# SCH_NFC-Business-Card_2025-01-12.net
KiCad netlist of a schematic drawn in EasyEDA
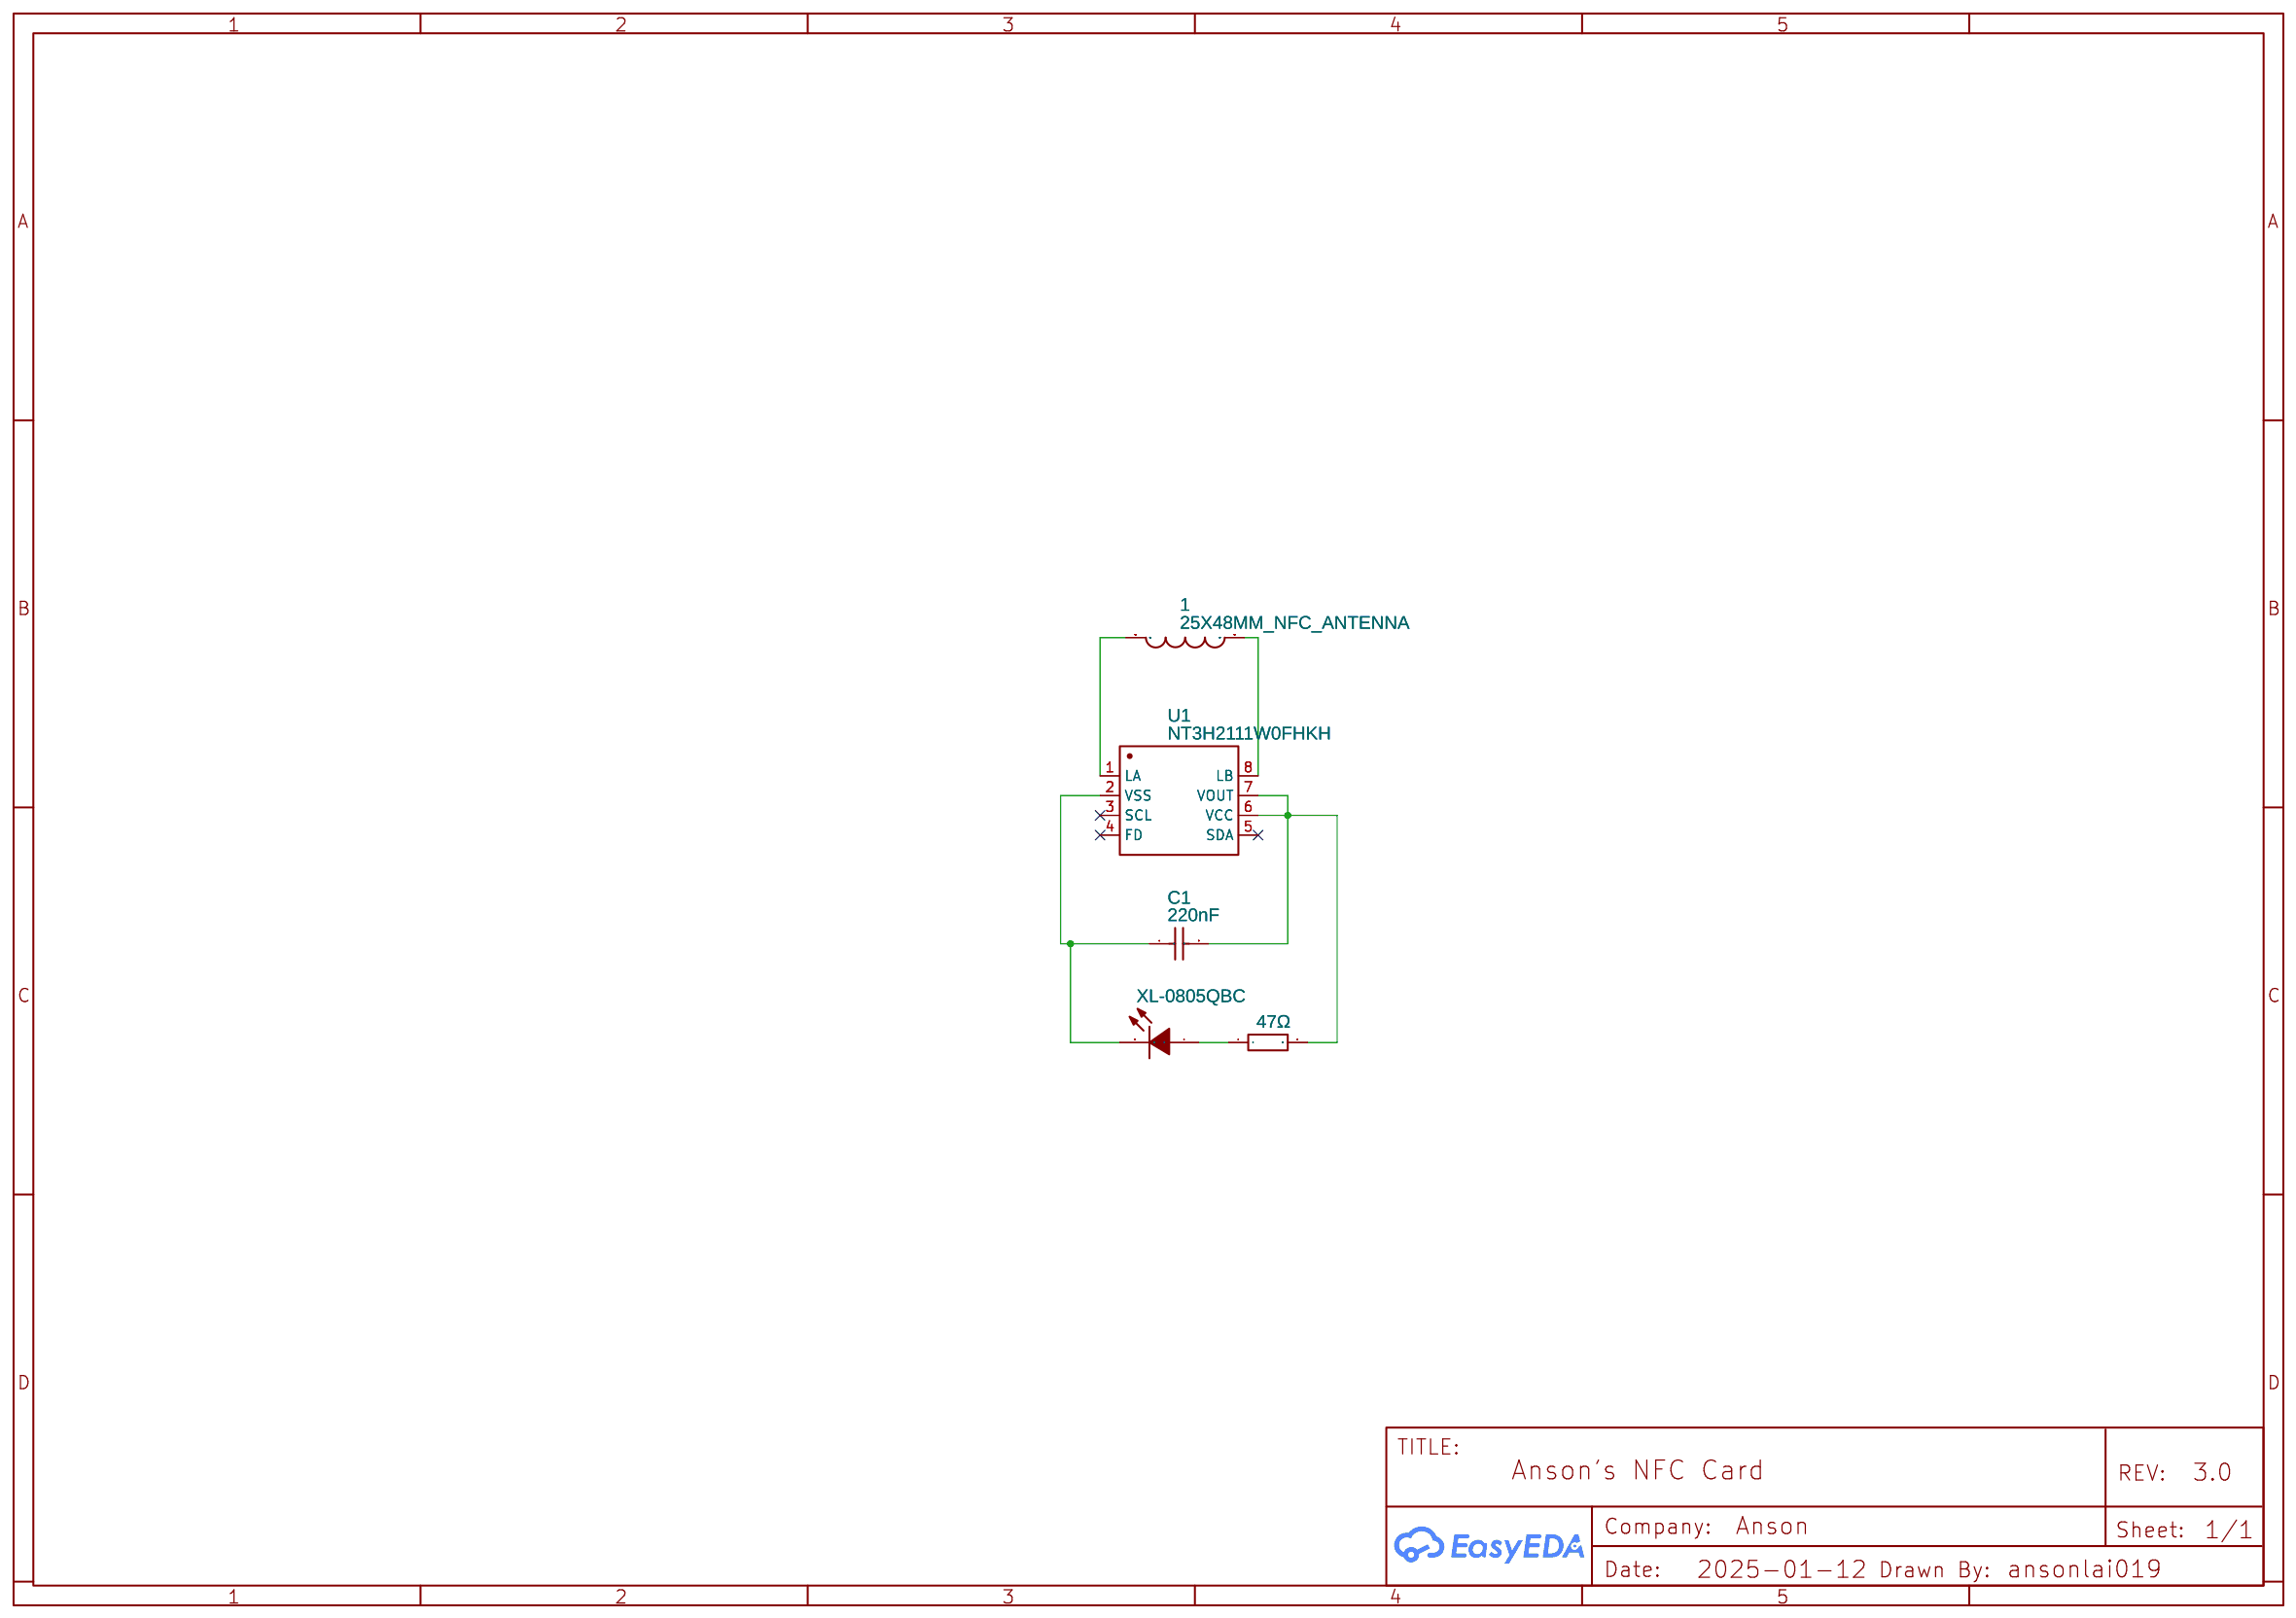
[diagram p0: schematic sheet]

(export (version "E")
  (design (tool "Eeschema 10.0.6"))
  (components
    (comp (ref "1") (value "25X48MM_NFC_ANTENNA") (libsource (lib "") (part "25X48MM_NFC_ANTENNA")))
    (comp (ref "C1")
      (value "220nF")
      (fields
        (field (name "Manufacturer Part") "CL10B224KA8NNNC")
        (field (name "Manufacturer") "SAMSUNG(三星)")
      )
      (libsource (lib "") (part "CL10B224KA8NNNC"))
    )
    (comp (ref "LED1")
      (value "XL-0805QBC")
      (fields (field (name "Manufacturer Part") "KT-0805B") (field (name "Manufacturer") "KENTO"))
      (libsource (lib "") (part "XL-0805QBC"))
    )
    (comp (ref "R1")
      (value "47Ω")
      (fields
        (field (name "Manufacturer Part") "0603WAF470JT5E")
        (field (name "Manufacturer") "UNI-ROYAL(厚声)")
      )
      (libsource (lib "") (part "0603WAF470JT5E"))
    )
    (comp (ref "U1")
      (value "NT3H2111W0FHKH")
      (fields (field (name "Manufacturer") "NXP(恩智浦)"))
      (libsource (lib "") (part "NT3H2111W0FHKH"))
    )
  )
  (nets
    (net (code "1") (name "Net-(LED1-A)") (class "Default")
      (node (ref "LED1") (pin "1") (pinfunction "A_1") (pintype "unspecified"))
      (node (ref "R1") (pin "1") (pinfunction "1_1") (pintype "input"))
    )
    (net (code "2") (name "Net-(LED1-K)") (class "Default")
      (node (ref "C1") (pin "1") (pinfunction "1_1") (pintype "input"))
      (node (ref "LED1") (pin "2") (pinfunction "K_2") (pintype "unspecified"))
      (node (ref "U1") (pin "2") (pinfunction "VSS_2") (pintype "unspecified"))
    )
    (net (code "3") (name "Net-(U1-LA)") (class "Default")
      (node (ref "1") (pin "P$2") (pinfunction "P$2_P$2") (pintype "bidirectional"))
      (node (ref "U1") (pin "1") (pinfunction "LA_1") (pintype "unspecified"))
    )
    (net (code "4") (name "Net-(U1-LB)") (class "Default")
      (node (ref "1") (pin "P$1") (pinfunction "P$1_P$1") (pintype "bidirectional"))
      (node (ref "U1") (pin "8") (pinfunction "LB_8") (pintype "unspecified"))
    )
    (net (code "5") (name "Net-(U1-VCC)") (class "Default")
      (node (ref "C1") (pin "2") (pinfunction "2_2") (pintype "input"))
      (node (ref "R1") (pin "2") (pinfunction "2_2") (pintype "input"))
      (node (ref "U1") (pin "6") (pinfunction "VCC_6") (pintype "unspecified"))
      (node (ref "U1") (pin "7") (pinfunction "VOUT_7") (pintype "unspecified"))
    )
    (net (code "6") (name "unconnected-(U1-FD-Pad4)") (class "Default")
      (node (ref "U1") (pin "4") (pinfunction "FD_4") (pintype "unspecified+no_connect"))
    )
    (net (code "7") (name "unconnected-(U1-SCL-Pad3)") (class "Default")
      (node (ref "U1") (pin "3") (pinfunction "SCL_3") (pintype "unspecified+no_connect"))
    )
    (net (code "8") (name "unconnected-(U1-SDA-Pad5)") (class "Default")
      (node (ref "U1") (pin "5") (pinfunction "SDA_5") (pintype "unspecified+no_connect"))
    )
  )
)
